# QUTMS-TSAL2-S04.net
KiCad netlist of a schematic drawn in Altium Designer
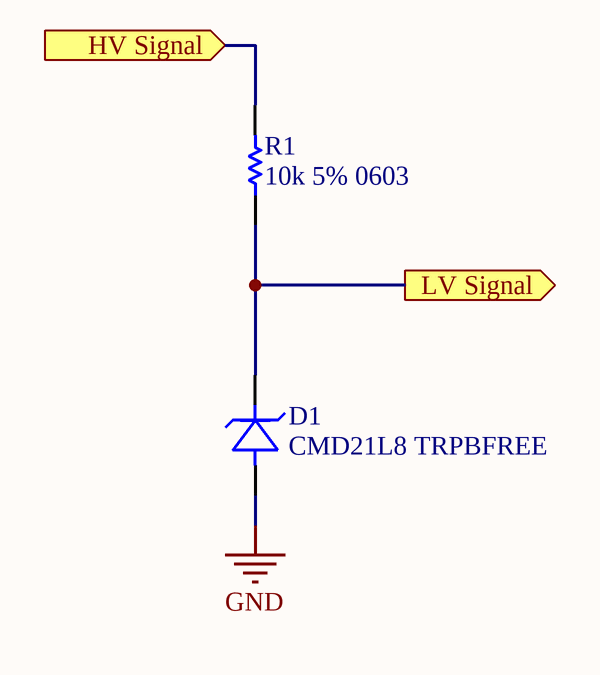
[diagram p0: QUTMS-TSAL2-S04.SchDoc]

(export (version "E")
  (design (tool "Eeschema 10.0.6"))
  (components
    (comp (ref "D1")
      (value "CMD21L8 TRPBFREE")
      (footprint "SODFL160X80-2N(Zener)")
      (libsource (lib "TSALdrive") (part "CMD21L8 TRPBFREE"))
    )
    (comp (ref "R1")
      (value "10k 5% 0603")
      (footprint "Res_ThinFilm_0603 (1,10k)")
      (description "Resistor, SMD, 10k, 0.1W, 5%, 0603")
      (libsource (lib "TSALdrive") (part "10k 5% 0603"))
    )
  )
  (nets
    (net (code "1") (name "/HV Signal") (class "Default")
      (node (ref "R1") (pin "2") (pinfunction "2_2") (pintype "passive"))
    )
    (net (code "2") (name "/LV Signal") (class "Default")
      (node (ref "D1") (pin "K") (pinfunction "Cathode_K") (pintype "passive"))
      (node (ref "R1") (pin "1") (pinfunction "1_1") (pintype "passive"))
    )
    (net (code "3") (name "GND") (class "Default")
      (node (ref "D1") (pin "A") (pinfunction "Anode_A") (pintype "passive"))
    )
  )
)
